# OZ440-SE100-CAR003_sheet9.net
KiCad netlist of a schematic drawn in Altium Designer
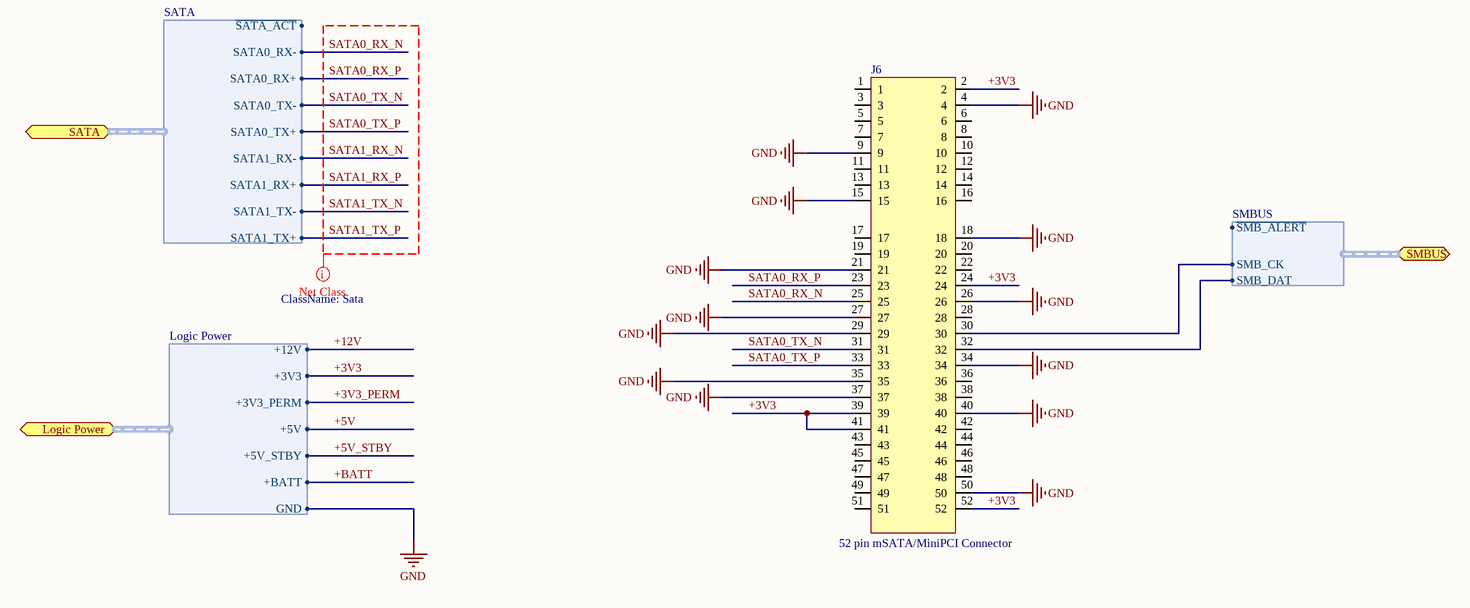
[diagram p0: OZ440-SE100-CAR003_sheet9.SchDoc]

(export (version "E")
  (design (tool "Eeschema 10.0.6"))
  (components
    (comp (ref "J6")
      (value "CONN-STD-miniPCI_msata")
      (footprint "CONN-SPE_MiniPCI-mSATA_MOLEX_67910-0002")
      (description "miniPCI / mSATA connector")
      (fields
        (field (name "DISPLAYED REFERENCE") "52 pin mSATA/MiniPCI Connector")
        (field (name "MANUFACTURER") "MOLEX")
      )
      (libsource (lib "lib_NAIO") (part "CONN-STD-miniPCI_msata"))
    )
  )
  (nets
    (net (code "5") (name "/+3V3") (class "Default")
      (node (ref "J6") (pin "2") (pinfunction "2_2") (pintype "passive"))
      (node (ref "J6") (pin "24") (pinfunction "24_24") (pintype "passive"))
      (node (ref "J6") (pin "39") (pinfunction "39_39") (pintype "passive"))
      (node (ref "J6") (pin "41") (pinfunction "41_41") (pintype "passive"))
      (node (ref "J6") (pin "52") (pinfunction "52_52") (pintype "passive"))
    )
    (net (code "11") (name "/SATA0_RX_N") (class "Default")
      (node (ref "J6") (pin "25") (pinfunction "25_25") (pintype "passive"))
    )
    (net (code "12") (name "/SATA0_RX_P") (class "Default")
      (node (ref "J6") (pin "23") (pinfunction "23_23") (pintype "passive"))
    )
    (net (code "13") (name "/SATA0_TX_N") (class "Default")
      (node (ref "J6") (pin "31") (pinfunction "31_31") (pintype "passive"))
    )
    (net (code "14") (name "/SATA0_TX_P") (class "Default")
      (node (ref "J6") (pin "33") (pinfunction "33_33") (pintype "passive"))
    )
    (net (code "19") (name "/SMB_CK") (class "Default")
      (node (ref "J6") (pin "30") (pinfunction "30_30") (pintype "passive"))
    )
    (net (code "20") (name "/SMB_DAT") (class "Default")
      (node (ref "J6") (pin "32") (pinfunction "32_32") (pintype "passive"))
    )
    (net (code "24") (name "GND") (class "Default")
      (node (ref "J6") (pin "15") (pinfunction "15_15") (pintype "passive"))
      (node (ref "J6") (pin "18") (pinfunction "18_18") (pintype "passive"))
      (node (ref "J6") (pin "21") (pinfunction "21_21") (pintype "passive"))
      (node (ref "J6") (pin "26") (pinfunction "26_26") (pintype "passive"))
      (node (ref "J6") (pin "27") (pinfunction "27_27") (pintype "passive"))
      (node (ref "J6") (pin "29") (pinfunction "29_29") (pintype "passive"))
      (node (ref "J6") (pin "34") (pinfunction "34_34") (pintype "passive"))
      (node (ref "J6") (pin "35") (pinfunction "35_35") (pintype "passive"))
      (node (ref "J6") (pin "37") (pinfunction "37_37") (pintype "passive"))
      (node (ref "J6") (pin "4") (pinfunction "4_4") (pintype "passive"))
      (node (ref "J6") (pin "40") (pinfunction "40_40") (pintype "passive"))
      (node (ref "J6") (pin "50") (pinfunction "50_50") (pintype "passive"))
      (node (ref "J6") (pin "9") (pinfunction "9_9") (pintype "passive"))
    )
    (net (code "25") (name "unconnected-(J6-Pad1)") (class "Default")
      (node (ref "J6") (pin "1") (pinfunction "1_1") (pintype "passive"))
    )
    (net (code "26") (name "unconnected-(J6-Pad3)") (class "Default")
      (node (ref "J6") (pin "3") (pinfunction "3_3") (pintype "passive"))
    )
    (net (code "27") (name "unconnected-(J6-Pad5)") (class "Default")
      (node (ref "J6") (pin "5") (pinfunction "5_5") (pintype "passive"))
    )
    (net (code "28") (name "unconnected-(J6-Pad6)") (class "Default")
      (node (ref "J6") (pin "6") (pinfunction "6_6") (pintype "passive"))
    )
    (net (code "29") (name "unconnected-(J6-Pad7)") (class "Default")
      (node (ref "J6") (pin "7") (pinfunction "7_7") (pintype "passive"))
    )
    (net (code "30") (name "unconnected-(J6-Pad8)") (class "Default")
      (node (ref "J6") (pin "8") (pinfunction "8_8") (pintype "passive"))
    )
    (net (code "31") (name "unconnected-(J6-Pad10)") (class "Default")
      (node (ref "J6") (pin "10") (pinfunction "10_10") (pintype "passive"))
    )
    (net (code "32") (name "unconnected-(J6-Pad11)") (class "Default")
      (node (ref "J6") (pin "11") (pinfunction "11_11") (pintype "passive"))
    )
    (net (code "33") (name "unconnected-(J6-Pad12)") (class "Default")
      (node (ref "J6") (pin "12") (pinfunction "12_12") (pintype "passive"))
    )
    (net (code "34") (name "unconnected-(J6-Pad13)") (class "Default")
      (node (ref "J6") (pin "13") (pinfunction "13_13") (pintype "passive"))
    )
    (net (code "35") (name "unconnected-(J6-Pad14)") (class "Default")
      (node (ref "J6") (pin "14") (pinfunction "14_14") (pintype "passive"))
    )
    (net (code "36") (name "unconnected-(J6-Pad16)") (class "Default")
      (node (ref "J6") (pin "16") (pinfunction "16_16") (pintype "passive"))
    )
    (net (code "37") (name "unconnected-(J6-Pad17)") (class "Default")
      (node (ref "J6") (pin "17") (pinfunction "17_17") (pintype "passive"))
    )
    (net (code "38") (name "unconnected-(J6-Pad19)") (class "Default")
      (node (ref "J6") (pin "19") (pinfunction "19_19") (pintype "passive"))
    )
    (net (code "39") (name "unconnected-(J6-Pad20)") (class "Default")
      (node (ref "J6") (pin "20") (pinfunction "20_20") (pintype "passive"))
    )
    (net (code "40") (name "unconnected-(J6-Pad22)") (class "Default")
      (node (ref "J6") (pin "22") (pinfunction "22_22") (pintype "passive"))
    )
    (net (code "41") (name "unconnected-(J6-Pad28)") (class "Default")
      (node (ref "J6") (pin "28") (pinfunction "28_28") (pintype "passive"))
    )
    (net (code "42") (name "unconnected-(J6-Pad36)") (class "Default")
      (node (ref "J6") (pin "36") (pinfunction "36_36") (pintype "passive"))
    )
    (net (code "43") (name "unconnected-(J6-Pad38)") (class "Default")
      (node (ref "J6") (pin "38") (pinfunction "38_38") (pintype "passive"))
    )
    (net (code "44") (name "unconnected-(J6-Pad42)") (class "Default")
      (node (ref "J6") (pin "42") (pinfunction "42_42") (pintype "passive"))
    )
    (net (code "45") (name "unconnected-(J6-Pad43)") (class "Default")
      (node (ref "J6") (pin "43") (pinfunction "43_43") (pintype "passive"))
    )
    (net (code "46") (name "unconnected-(J6-Pad44)") (class "Default")
      (node (ref "J6") (pin "44") (pinfunction "44_44") (pintype "passive"))
    )
    (net (code "47") (name "unconnected-(J6-Pad45)") (class "Default")
      (node (ref "J6") (pin "45") (pinfunction "45_45") (pintype "passive"))
    )
    (net (code "48") (name "unconnected-(J6-Pad46)") (class "Default")
      (node (ref "J6") (pin "46") (pinfunction "46_46") (pintype "passive"))
    )
    (net (code "49") (name "unconnected-(J6-Pad47)") (class "Default")
      (node (ref "J6") (pin "47") (pinfunction "47_47") (pintype "passive"))
    )
    (net (code "50") (name "unconnected-(J6-Pad48)") (class "Default")
      (node (ref "J6") (pin "48") (pinfunction "48_48") (pintype "passive"))
    )
    (net (code "51") (name "unconnected-(J6-Pad49)") (class "Default")
      (node (ref "J6") (pin "49") (pinfunction "49_49") (pintype "passive"))
    )
    (net (code "52") (name "unconnected-(J6-Pad51)") (class "Default")
      (node (ref "J6") (pin "51") (pinfunction "51_51") (pintype "passive"))
    )
  )
)
